# RTCMK_RTC.net
KiCad netlist of a schematic drawn in Altium Designer
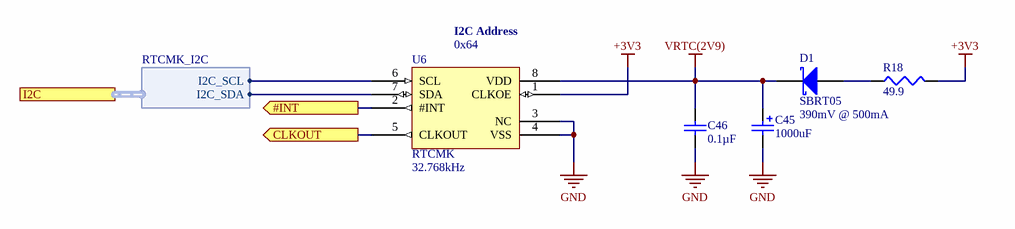
[diagram p0: RTCMK RTC.SchDoc]

(export (version "E")
  (design (tool "Eeschema 10.0.6"))
  (components
    (comp (ref "C45")
      (value "1000uF")
      (footprint "AVX-F722824M")
      (description "CAP TANT 1000UF 10V 20% 2824")
      (fields
        (field (name "PART NUMBER") "PC-AVX-00233")
        (field (name "MANUFACTURER PART NUMBER") "F721A108MMCAQ2")
        (field (name "PUBLISHER") "AlbertaSat")
      )
      (libsource (lib "Database") (part "Cap Pol1"))
    )
    (comp (ref "C46")
      (value "0.1µF")
      (footprint "TDK-CGA2B")
      (description "CAP CER 0.1UF 50V X7R 0402")
      (fields
        (field (name "PART NUMBER") "PC-TDK-02259")
        (field (name "MANUFACTURER PART NUMBER") "CGA2B3X7R1H104K050BB")
        (field (name "PUBLISHER") "AlbertaSat")
      )
      (libsource (lib "Database") (part "Cap"))
    )
    (comp (ref "D1")
      (value "SBRT05")
      (footprint "DIOD-X2-DFN1006-2")
      (description "SUPER BARRIER RECTIFIER X2-DFN10")
      (fields
        (field (name "PART NUMBER") "29")
        (field (name "MANUFACTURER PART NUMBER") "SBRT05U20LPS-7B")
        (field (name "VOLTAGE - FORWARD (MAX)") "390mV @ 500mA")
        (field (name "PUBLISHER") "Altium Limited")
      )
      (libsource (lib "Database") (part "D Schottky"))
    )
    (comp (ref "R18")
      (value "49.9")
      (footprint "PANA-ERJ2R")
      (description "RES SMD 49.9 OHM 1% 1/10W 0402")
      (fields
        (field (name "PART NUMBER") "13732")
        (field (name "MANUFACTURER PART NUMBER") "ERJ-2RKF49R9X")
        (field (name "PUBLISHER") "Altium Limited")
      )
      (libsource (lib "Database") (part "Res3"))
    )
    (comp (ref "U6")
      (value "RTCMK")
      (footprint "ABR-RTCMK")
      (description "IC RTC CLK/CALENDAR I2C 8-SMT")
      (fields
        (field (name "PART NUMBER") "PU-ABR-00037")
        (field (name "MANUFACTURER PART NUMBER") "AB-RTCMK-32.768KHZ-T3")
        (field (name "ALTIUM_VALUE") "32.768kHz")
        (field (name "PUBLISHER") "AlbertaSat")
      )
      (libsource (lib "Database") (part "RTCMK"))
    )
  )
  (nets
    (net (code "2") (name "+3V3") (class "Default")
      (node (ref "R18") (pin "2") (pinfunction "2_2") (pintype "passive"))
      (node (ref "U6") (pin "1") (pinfunction "CLKOE_1") (pintype "bidirectional"))
    )
    (net (code "3") (name "/#INT") (class "Default")
      (node (ref "U6") (pin "2") (pinfunction "#INT_2") (pintype "output"))
    )
    (net (code "4") (name "/CLKOUT") (class "Default")
      (node (ref "U6") (pin "5") (pinfunction "CLKOUT_5") (pintype "output"))
    )
    (net (code "5") (name "/I2C_SCL") (class "Default")
      (node (ref "U6") (pin "6") (pinfunction "SCL_6") (pintype "input"))
    )
    (net (code "6") (name "/I2C_SDA") (class "Default")
      (node (ref "U6") (pin "7") (pinfunction "SDA_7") (pintype "bidirectional"))
    )
    (net (code "8") (name "GND") (class "Default")
      (node (ref "C45") (pin "2") (pinfunction "2_2") (pintype "passive"))
      (node (ref "C46") (pin "2") (pinfunction "2_2") (pintype "passive"))
      (node (ref "U6") (pin "3") (pinfunction "NC_3") (pintype "passive"))
      (node (ref "U6") (pin "4") (pinfunction "VSS_4") (pintype "power_in"))
    )
    (net (code "9") (name "Net-(D1-A)") (class "Default")
      (node (ref "D1") (pin "1") (pinfunction "A_1") (pintype "passive"))
      (node (ref "R18") (pin "1") (pinfunction "1_1") (pintype "passive"))
    )
    (net (code "10") (name "VRTC(2V9)") (class "Default")
      (node (ref "C45") (pin "1") (pinfunction "1_1") (pintype "passive"))
      (node (ref "C46") (pin "1") (pinfunction "1_1") (pintype "passive"))
      (node (ref "D1") (pin "2") (pinfunction "K_2") (pintype "passive"))
      (node (ref "U6") (pin "8") (pinfunction "VDD_8") (pintype "power_in"))
    )
  )
)
